# powerctl.net
KiCad netlist of a schematic drawn in EAGLE
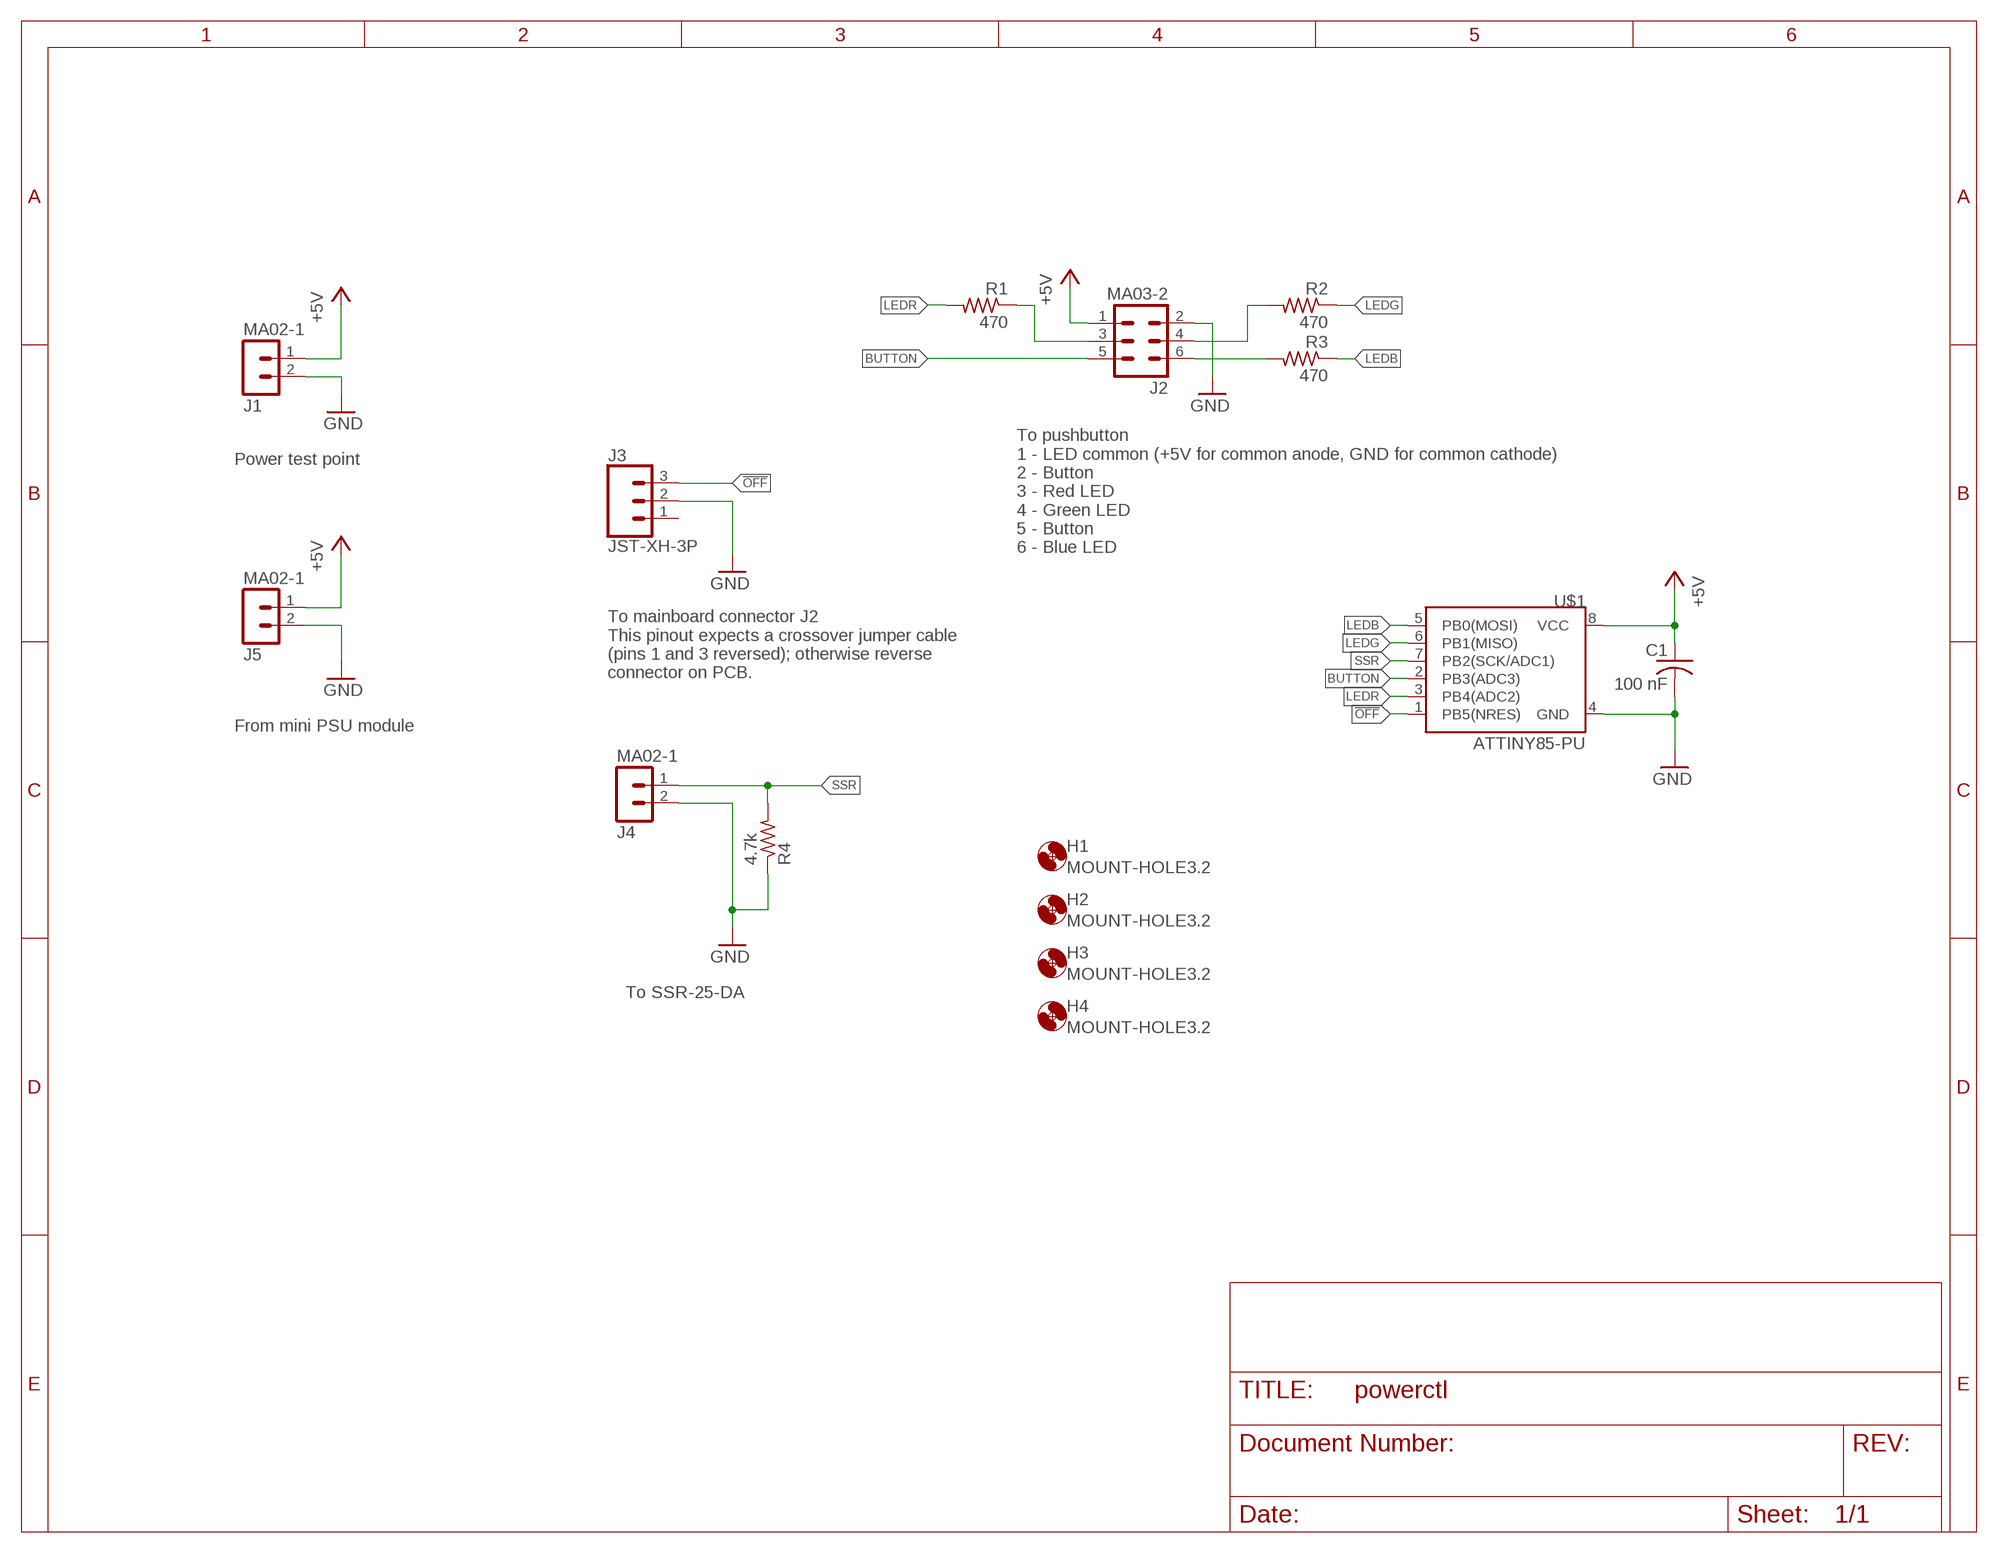
[diagram p0: schematic, sheet 1]

(export (version "E")
  (design (tool "Eeschema 10.0.6"))
  (components
    (comp (ref "C1")
      (value "100 nF")
      (footprint "eagle-import:C025-025X050")
      (libsource (lib "eagle-import") (part "C-US025-025X050"))
    )
    (comp (ref "H1")
      (value "MOUNT-HOLE3.2")
      (footprint "eagle-import:3,2")
      (libsource (lib "eagle-import") (part "MOUNT-HOLE3.2"))
    )
    (comp (ref "H2")
      (value "MOUNT-HOLE3.2")
      (footprint "eagle-import:3,2")
      (libsource (lib "eagle-import") (part "MOUNT-HOLE3.2"))
    )
    (comp (ref "H3")
      (value "MOUNT-HOLE3.2")
      (footprint "eagle-import:3,2")
      (libsource (lib "eagle-import") (part "MOUNT-HOLE3.2"))
    )
    (comp (ref "H4")
      (value "MOUNT-HOLE3.2")
      (footprint "eagle-import:3,2")
      (libsource (lib "eagle-import") (part "MOUNT-HOLE3.2"))
    )
    (comp (ref "J1")
      (value "MA02-1")
      (footprint "eagle-import:MA02-1")
      (libsource (lib "eagle-import") (part "MA02-1"))
    )
    (comp (ref "J2")
      (value "MA03-2")
      (footprint "eagle-import:MA03-2")
      (libsource (lib "eagle-import") (part "MA03-2"))
    )
    (comp (ref "J3")
      (value "JST-XH-3P")
      (footprint "eagle-import:JST-3-PTH-VERT")
      (libsource (lib "eagle-import") (part "CONN_03JST-PTH-VERT"))
    )
    (comp (ref "J4")
      (value "MA02-1")
      (footprint "eagle-import:MA02-1")
      (libsource (lib "eagle-import") (part "MA02-1"))
    )
    (comp (ref "J5")
      (value "MA02-1")
      (footprint "eagle-import:MA02-1")
      (libsource (lib "eagle-import") (part "MA02-1"))
    )
    (comp (ref "R1")
      (value "470")
      (footprint "eagle-import:0204_7")
      (libsource (lib "eagle-import") (part "R-US_0204/7"))
    )
    (comp (ref "R2")
      (value "470")
      (footprint "eagle-import:0204_7")
      (libsource (lib "eagle-import") (part "R-US_0204/7"))
    )
    (comp (ref "R3")
      (value "470")
      (footprint "eagle-import:0204_7")
      (libsource (lib "eagle-import") (part "R-US_0204/7"))
    )
    (comp (ref "R4")
      (value "4.7k")
      (footprint "eagle-import:0204_7")
      (libsource (lib "eagle-import") (part "R-US_0204/7"))
    )
    (comp (ref "U$1")
      (value "ATTINY85-PU")
      (footprint "eagle-import:DIP08")
      (libsource (lib "eagle-import") (part "ATTINY13DIP"))
    )
  )
  (nets
    (net (code "1") (name "+5V") (class "Default")
      (node (ref "C1") (pin "1") (pinfunction "1_1") (pintype "passive"))
      (node (ref "J1") (pin "1") (pinfunction "1_1") (pintype "passive"))
      (node (ref "J2") (pin "1") (pinfunction "1_1") (pintype "passive"))
      (node (ref "J5") (pin "1") (pinfunction "1_1") (pintype "passive"))
      (node (ref "U$1") (pin "8") (pinfunction "VCC_8") (pintype "bidirectional"))
    )
    (net (code "2") (name "/~{OFF}") (class "Default")
      (node (ref "J3") (pin "3") (pinfunction "3_3") (pintype "passive"))
      (node (ref "U$1") (pin "1") (pinfunction "PB5(NRES)_1") (pintype "bidirectional"))
    )
    (net (code "3") (name "BUTTON") (class "Default")
      (node (ref "J2") (pin "5") (pinfunction "5_5") (pintype "passive"))
      (node (ref "U$1") (pin "2") (pinfunction "PB3(ADC3)_2") (pintype "bidirectional"))
    )
    (net (code "4") (name "GND") (class "Default")
      (node (ref "C1") (pin "2") (pinfunction "2_2") (pintype "passive"))
      (node (ref "J1") (pin "2") (pinfunction "2_2") (pintype "passive"))
      (node (ref "J2") (pin "2") (pinfunction "2_2") (pintype "passive"))
      (node (ref "J3") (pin "2") (pinfunction "2_2") (pintype "passive"))
      (node (ref "J4") (pin "2") (pinfunction "2_2") (pintype "passive"))
      (node (ref "J5") (pin "2") (pinfunction "2_2") (pintype "passive"))
      (node (ref "R4") (pin "1") (pinfunction "1_1") (pintype "passive"))
      (node (ref "U$1") (pin "4") (pinfunction "GND_4") (pintype "bidirectional"))
    )
    (net (code "5") (name "LEDB") (class "Default")
      (node (ref "R3") (pin "1") (pinfunction "1_1") (pintype "passive"))
      (node (ref "U$1") (pin "5") (pinfunction "PB0(MOSI)_5") (pintype "bidirectional"))
    )
    (net (code "6") (name "LEDG") (class "Default")
      (node (ref "R2") (pin "1") (pinfunction "1_1") (pintype "passive"))
      (node (ref "U$1") (pin "6") (pinfunction "PB1(MISO)_6") (pintype "bidirectional"))
    )
    (net (code "7") (name "LEDR") (class "Default")
      (node (ref "R1") (pin "2") (pinfunction "2_2") (pintype "passive"))
      (node (ref "U$1") (pin "3") (pinfunction "PB4(ADC2)_3") (pintype "bidirectional"))
    )
    (net (code "8") (name "Net-(J2-Pad3)") (class "Default")
      (node (ref "J2") (pin "3") (pinfunction "3_3") (pintype "passive"))
      (node (ref "R1") (pin "1") (pinfunction "1_1") (pintype "passive"))
    )
    (net (code "9") (name "Net-(J2-Pad4)") (class "Default")
      (node (ref "J2") (pin "4") (pinfunction "4_4") (pintype "passive"))
      (node (ref "R2") (pin "2") (pinfunction "2_2") (pintype "passive"))
    )
    (net (code "10") (name "Net-(J2-Pad6)") (class "Default")
      (node (ref "J2") (pin "6") (pinfunction "6_6") (pintype "passive"))
      (node (ref "R3") (pin "2") (pinfunction "2_2") (pintype "passive"))
    )
    (net (code "11") (name "SSR") (class "Default")
      (node (ref "J4") (pin "1") (pinfunction "1_1") (pintype "passive"))
      (node (ref "R4") (pin "2") (pinfunction "2_2") (pintype "passive"))
      (node (ref "U$1") (pin "7") (pinfunction "PB2(SCK/ADC1)_7") (pintype "bidirectional"))
    )
    (net (code "12") (name "unconnected-(J3-Pad1)") (class "Default")
      (node (ref "J3") (pin "1") (pinfunction "1_1") (pintype "passive"))
    )
  )
)
